# M051B.net
KiCad netlist of a schematic drawn in EAGLE
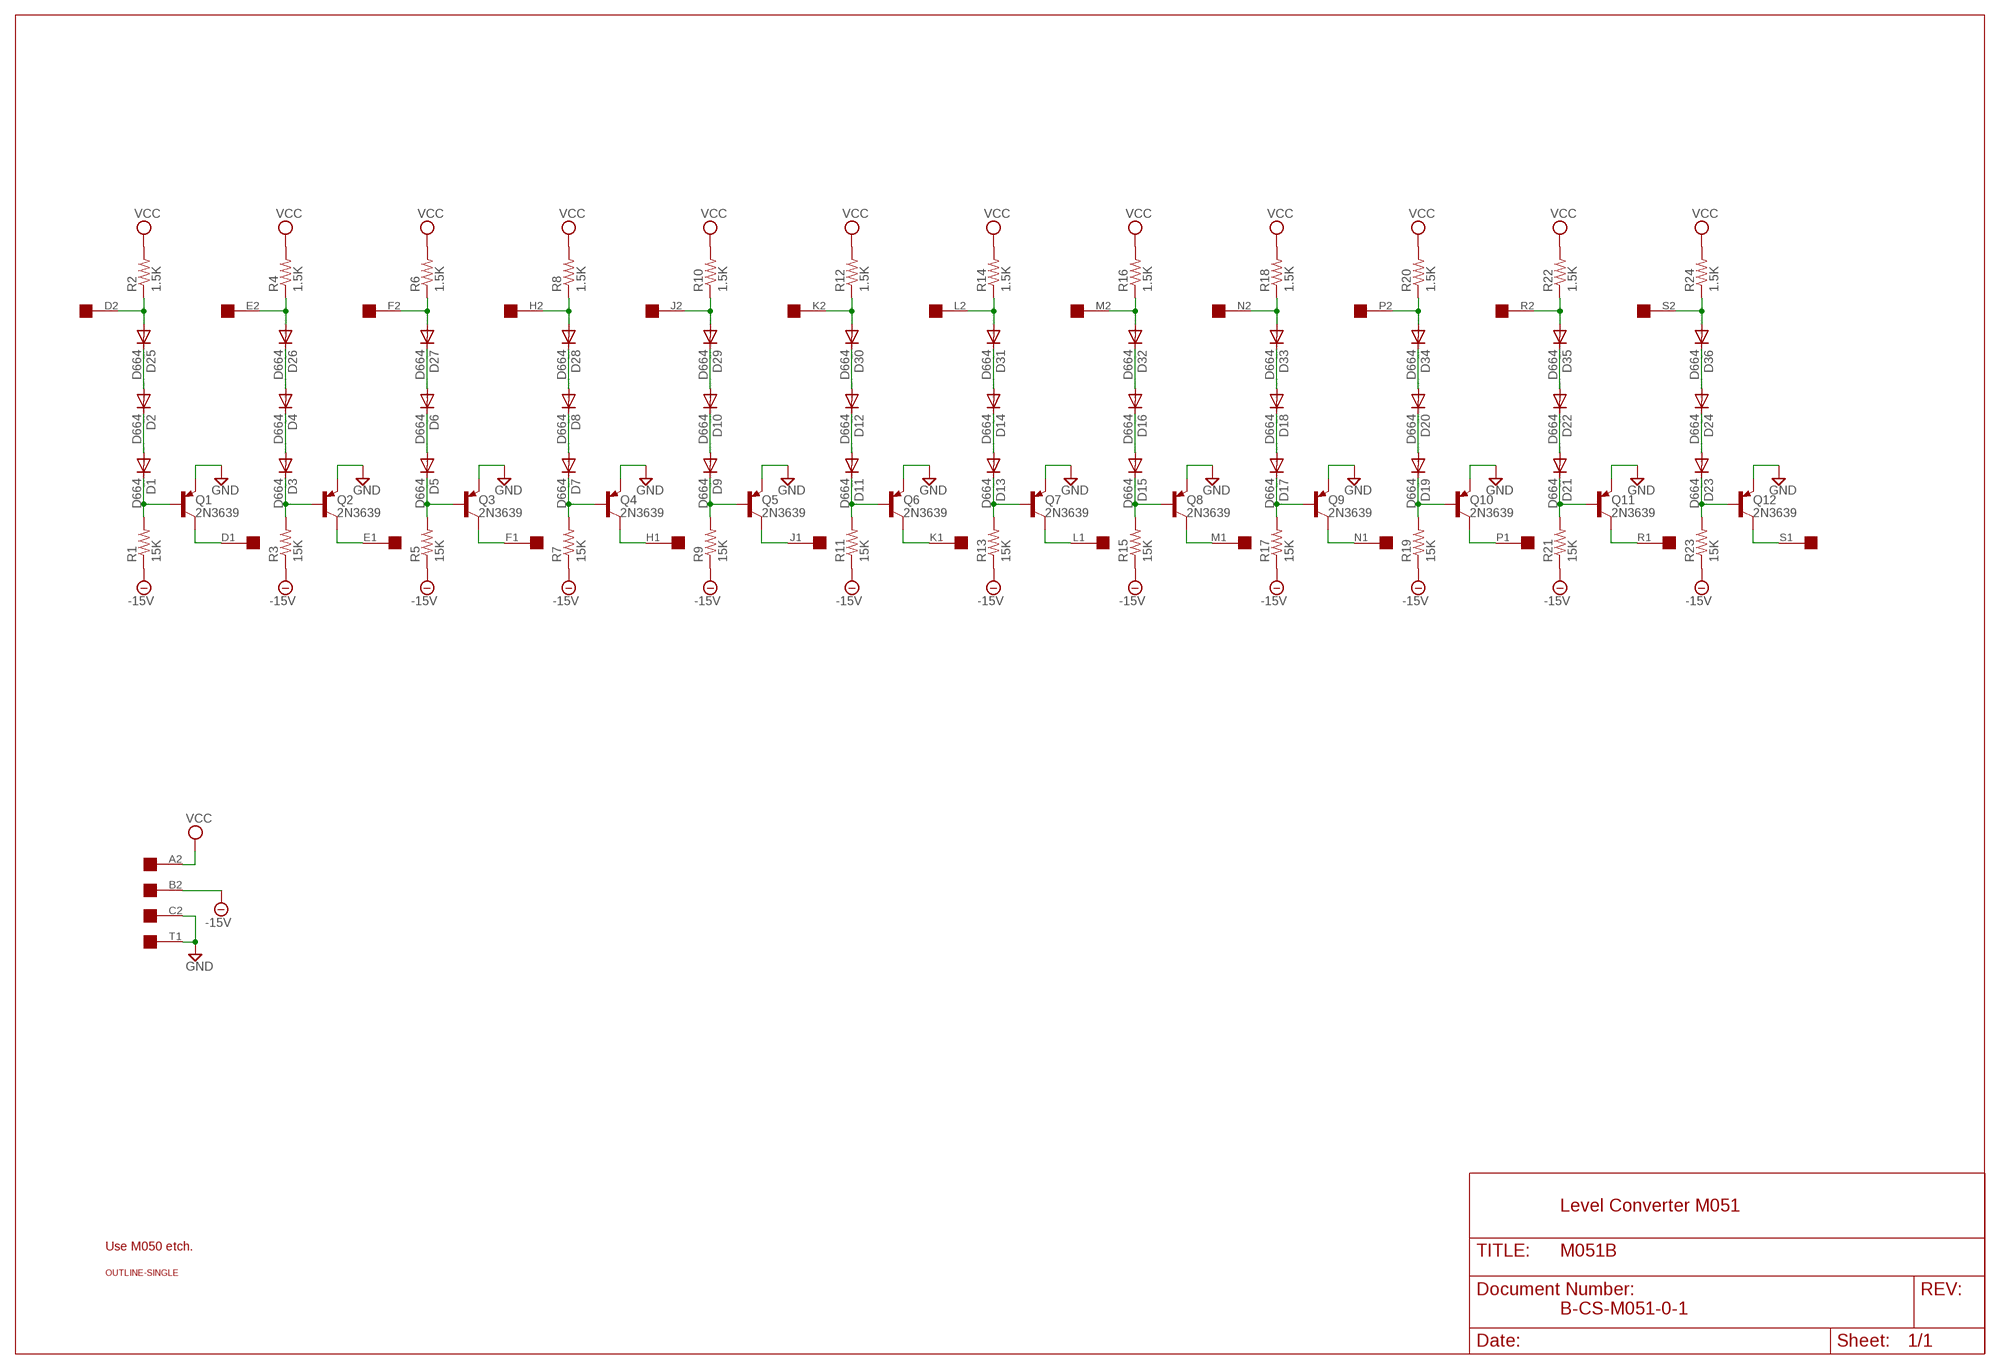
[diagram p0: schematic, sheet 1]

(export (version "E")
  (design (tool "Eeschema 10.0.6"))
  (components
    (comp (ref "D1")
      (value "D664")
      (footprint "eagle-import:DO35-10")
      (libsource (lib "eagle-import") (part "DIODE-DO35-10"))
    )
    (comp (ref "D2")
      (value "D664")
      (footprint "eagle-import:DO35-10")
      (libsource (lib "eagle-import") (part "DIODE-DO35-10"))
    )
    (comp (ref "D3")
      (value "D664")
      (footprint "eagle-import:DO35-10")
      (libsource (lib "eagle-import") (part "DIODE-DO35-10"))
    )
    (comp (ref "D4")
      (value "D664")
      (footprint "eagle-import:DO35-10")
      (libsource (lib "eagle-import") (part "DIODE-DO35-10"))
    )
    (comp (ref "D5")
      (value "D664")
      (footprint "eagle-import:DO35-10")
      (libsource (lib "eagle-import") (part "DIODE-DO35-10"))
    )
    (comp (ref "D6")
      (value "D664")
      (footprint "eagle-import:DO35-10")
      (libsource (lib "eagle-import") (part "DIODE-DO35-10"))
    )
    (comp (ref "D7")
      (value "D664")
      (footprint "eagle-import:DO35-10")
      (libsource (lib "eagle-import") (part "DIODE-DO35-10"))
    )
    (comp (ref "D8")
      (value "D664")
      (footprint "eagle-import:DO35-10")
      (libsource (lib "eagle-import") (part "DIODE-DO35-10"))
    )
    (comp (ref "D9")
      (value "D664")
      (footprint "eagle-import:DO35-10")
      (libsource (lib "eagle-import") (part "DIODE-DO35-10"))
    )
    (comp (ref "D10")
      (value "D664")
      (footprint "eagle-import:DO35-10")
      (libsource (lib "eagle-import") (part "DIODE-DO35-10"))
    )
    (comp (ref "D11")
      (value "D664")
      (footprint "eagle-import:DO35-10")
      (libsource (lib "eagle-import") (part "DIODE-DO35-10"))
    )
    (comp (ref "D12")
      (value "D664")
      (footprint "eagle-import:DO35-10")
      (libsource (lib "eagle-import") (part "DIODE-DO35-10"))
    )
    (comp (ref "D13")
      (value "D664")
      (footprint "eagle-import:DO35-10")
      (libsource (lib "eagle-import") (part "DIODE-DO35-10"))
    )
    (comp (ref "D14")
      (value "D664")
      (footprint "eagle-import:DO35-10")
      (libsource (lib "eagle-import") (part "DIODE-DO35-10"))
    )
    (comp (ref "D15")
      (value "D664")
      (footprint "eagle-import:DO35-10")
      (libsource (lib "eagle-import") (part "DIODE-DO35-10"))
    )
    (comp (ref "D16")
      (value "D664")
      (footprint "eagle-import:DO35-10")
      (libsource (lib "eagle-import") (part "DIODE-DO35-10"))
    )
    (comp (ref "D17")
      (value "D664")
      (footprint "eagle-import:DO35-10")
      (libsource (lib "eagle-import") (part "DIODE-DO35-10"))
    )
    (comp (ref "D18")
      (value "D664")
      (footprint "eagle-import:DO35-10")
      (libsource (lib "eagle-import") (part "DIODE-DO35-10"))
    )
    (comp (ref "D19")
      (value "D664")
      (footprint "eagle-import:DO35-10")
      (libsource (lib "eagle-import") (part "DIODE-DO35-10"))
    )
    (comp (ref "D20")
      (value "D664")
      (footprint "eagle-import:DO35-10")
      (libsource (lib "eagle-import") (part "DIODE-DO35-10"))
    )
    (comp (ref "D21")
      (value "D664")
      (footprint "eagle-import:DO35-10")
      (libsource (lib "eagle-import") (part "DIODE-DO35-10"))
    )
    (comp (ref "D22")
      (value "D664")
      (footprint "eagle-import:DO35-10")
      (libsource (lib "eagle-import") (part "DIODE-DO35-10"))
    )
    (comp (ref "D23")
      (value "D664")
      (footprint "eagle-import:DO35-10")
      (libsource (lib "eagle-import") (part "DIODE-DO35-10"))
    )
    (comp (ref "D24")
      (value "D664")
      (footprint "eagle-import:DO35-10")
      (libsource (lib "eagle-import") (part "DIODE-DO35-10"))
    )
    (comp (ref "D25")
      (value "D664")
      (footprint "eagle-import:DO35-10")
      (libsource (lib "eagle-import") (part "DIODE-DO35-10"))
    )
    (comp (ref "D26")
      (value "D664")
      (footprint "eagle-import:DO35-10")
      (libsource (lib "eagle-import") (part "DIODE-DO35-10"))
    )
    (comp (ref "D27")
      (value "D664")
      (footprint "eagle-import:DO35-10")
      (libsource (lib "eagle-import") (part "DIODE-DO35-10"))
    )
    (comp (ref "D28")
      (value "D664")
      (footprint "eagle-import:DO35-10")
      (libsource (lib "eagle-import") (part "DIODE-DO35-10"))
    )
    (comp (ref "D29")
      (value "D664")
      (footprint "eagle-import:DO35-10")
      (libsource (lib "eagle-import") (part "DIODE-DO35-10"))
    )
    (comp (ref "D30")
      (value "D664")
      (footprint "eagle-import:DO35-10")
      (libsource (lib "eagle-import") (part "DIODE-DO35-10"))
    )
    (comp (ref "D31")
      (value "D664")
      (footprint "eagle-import:DO35-10")
      (libsource (lib "eagle-import") (part "DIODE-DO35-10"))
    )
    (comp (ref "D32")
      (value "D664")
      (footprint "eagle-import:DO35-10")
      (libsource (lib "eagle-import") (part "DIODE-DO35-10"))
    )
    (comp (ref "D33")
      (value "D664")
      (footprint "eagle-import:DO35-10")
      (libsource (lib "eagle-import") (part "DIODE-DO35-10"))
    )
    (comp (ref "D34")
      (value "D664")
      (footprint "eagle-import:DO35-10")
      (libsource (lib "eagle-import") (part "DIODE-DO35-10"))
    )
    (comp (ref "D35")
      (value "D664")
      (footprint "eagle-import:DO35-10")
      (libsource (lib "eagle-import") (part "DIODE-DO35-10"))
    )
    (comp (ref "D36")
      (value "D664")
      (footprint "eagle-import:DO35-10")
      (libsource (lib "eagle-import") (part "DIODE-DO35-10"))
    )
    (comp (ref "Q1")
      (value "2N3639")
      (footprint "eagle-import:TO5")
      (libsource (lib "eagle-import") (part "-PNP-TO5"))
    )
    (comp (ref "Q2")
      (value "2N3639")
      (footprint "eagle-import:TO5")
      (libsource (lib "eagle-import") (part "-PNP-TO5"))
    )
    (comp (ref "Q3")
      (value "2N3639")
      (footprint "eagle-import:TO5")
      (libsource (lib "eagle-import") (part "-PNP-TO5"))
    )
    (comp (ref "Q4")
      (value "2N3639")
      (footprint "eagle-import:TO5")
      (libsource (lib "eagle-import") (part "-PNP-TO5"))
    )
    (comp (ref "Q5")
      (value "2N3639")
      (footprint "eagle-import:TO5")
      (libsource (lib "eagle-import") (part "-PNP-TO5"))
    )
    (comp (ref "Q6")
      (value "2N3639")
      (footprint "eagle-import:TO5")
      (libsource (lib "eagle-import") (part "-PNP-TO5"))
    )
    (comp (ref "Q7")
      (value "2N3639")
      (footprint "eagle-import:TO5")
      (libsource (lib "eagle-import") (part "-PNP-TO5"))
    )
    (comp (ref "Q8")
      (value "2N3639")
      (footprint "eagle-import:TO5")
      (libsource (lib "eagle-import") (part "-PNP-TO5"))
    )
    (comp (ref "Q9")
      (value "2N3639")
      (footprint "eagle-import:TO5")
      (libsource (lib "eagle-import") (part "-PNP-TO5"))
    )
    (comp (ref "Q10")
      (value "2N3639")
      (footprint "eagle-import:TO5")
      (libsource (lib "eagle-import") (part "-PNP-TO5"))
    )
    (comp (ref "Q11")
      (value "2N3639")
      (footprint "eagle-import:TO5")
      (libsource (lib "eagle-import") (part "-PNP-TO5"))
    )
    (comp (ref "Q12")
      (value "2N3639")
      (footprint "eagle-import:TO5")
      (libsource (lib "eagle-import") (part "-PNP-TO5"))
    )
    (comp (ref "R1")
      (value "15K")
      (footprint "eagle-import:0207_10")
      (libsource (lib "eagle-import") (part "R-US_0207/10"))
    )
    (comp (ref "R2")
      (value "1.5K")
      (footprint "eagle-import:0207_10")
      (libsource (lib "eagle-import") (part "R-US_0207/10"))
    )
    (comp (ref "R3")
      (value "15K")
      (footprint "eagle-import:0207_10")
      (libsource (lib "eagle-import") (part "R-US_0207/10"))
    )
    (comp (ref "R4")
      (value "1.5K")
      (footprint "eagle-import:0207_10")
      (libsource (lib "eagle-import") (part "R-US_0207/10"))
    )
    (comp (ref "R5")
      (value "15K")
      (footprint "eagle-import:0207_10")
      (libsource (lib "eagle-import") (part "R-US_0207/10"))
    )
    (comp (ref "R6")
      (value "1.5K")
      (footprint "eagle-import:0207_10")
      (libsource (lib "eagle-import") (part "R-US_0207/10"))
    )
    (comp (ref "R7")
      (value "15K")
      (footprint "eagle-import:0207_10")
      (libsource (lib "eagle-import") (part "R-US_0207/10"))
    )
    (comp (ref "R8")
      (value "1.5K")
      (footprint "eagle-import:0207_10")
      (libsource (lib "eagle-import") (part "R-US_0207/10"))
    )
    (comp (ref "R9")
      (value "15K")
      (footprint "eagle-import:0207_10")
      (libsource (lib "eagle-import") (part "R-US_0207/10"))
    )
    (comp (ref "R10")
      (value "1.5K")
      (footprint "eagle-import:0207_10")
      (libsource (lib "eagle-import") (part "R-US_0207/10"))
    )
    (comp (ref "R11")
      (value "15K")
      (footprint "eagle-import:0207_10")
      (libsource (lib "eagle-import") (part "R-US_0207/10"))
    )
    (comp (ref "R12")
      (value "1.5K")
      (footprint "eagle-import:0207_10")
      (libsource (lib "eagle-import") (part "R-US_0207/10"))
    )
    (comp (ref "R13")
      (value "15K")
      (footprint "eagle-import:0207_10")
      (libsource (lib "eagle-import") (part "R-US_0207/10"))
    )
    (comp (ref "R14")
      (value "1.5K")
      (footprint "eagle-import:0207_10")
      (libsource (lib "eagle-import") (part "R-US_0207/10"))
    )
    (comp (ref "R15")
      (value "15K")
      (footprint "eagle-import:0207_10")
      (libsource (lib "eagle-import") (part "R-US_0207/10"))
    )
    (comp (ref "R16")
      (value "1.5K")
      (footprint "eagle-import:0207_10")
      (libsource (lib "eagle-import") (part "R-US_0207/10"))
    )
    (comp (ref "R17")
      (value "15K")
      (footprint "eagle-import:0207_10")
      (libsource (lib "eagle-import") (part "R-US_0207/10"))
    )
    (comp (ref "R18")
      (value "1.5K")
      (footprint "eagle-import:0207_10")
      (libsource (lib "eagle-import") (part "R-US_0207/10"))
    )
    (comp (ref "R19")
      (value "15K")
      (footprint "eagle-import:0207_10")
      (libsource (lib "eagle-import") (part "R-US_0207/10"))
    )
    (comp (ref "R20")
      (value "1.5K")
      (footprint "eagle-import:0207_10")
      (libsource (lib "eagle-import") (part "R-US_0207/10"))
    )
    (comp (ref "R21")
      (value "15K")
      (footprint "eagle-import:0207_10")
      (libsource (lib "eagle-import") (part "R-US_0207/10"))
    )
    (comp (ref "R22")
      (value "1.5K")
      (footprint "eagle-import:0207_10")
      (libsource (lib "eagle-import") (part "R-US_0207/10"))
    )
    (comp (ref "R23")
      (value "15K")
      (footprint "eagle-import:0207_10")
      (libsource (lib "eagle-import") (part "R-US_0207/10"))
    )
    (comp (ref "R24")
      (value "1.5K")
      (footprint "eagle-import:0207_10")
      (libsource (lib "eagle-import") (part "R-US_0207/10"))
    )
    (comp (ref "U$1")
      (value "OUTLINE-SINGLE")
      (footprint "eagle-import:SINGLE")
      (libsource (lib "eagle-import") (part "OUTLINE-SINGLE"))
    )
    (comp (ref "U$2")
      (value "SINGLE")
      (footprint "eagle-import:EDGE-CON2")
      (libsource (lib "eagle-import") (part "SINGLE"))
    )
  )
  (nets
    (net (code "1") (name "-15V") (class "Default")
      (node (ref "R1") (pin "1") (pinfunction "1_1") (pintype "passive"))
      (node (ref "R11") (pin "1") (pinfunction "1_1") (pintype "passive"))
      (node (ref "R13") (pin "1") (pinfunction "1_1") (pintype "passive"))
      (node (ref "R15") (pin "1") (pinfunction "1_1") (pintype "passive"))
      (node (ref "R17") (pin "1") (pinfunction "1_1") (pintype "passive"))
      (node (ref "R19") (pin "1") (pinfunction "1_1") (pintype "passive"))
      (node (ref "R21") (pin "1") (pinfunction "1_1") (pintype "passive"))
      (node (ref "R23") (pin "1") (pinfunction "1_1") (pintype "passive"))
      (node (ref "R3") (pin "1") (pinfunction "1_1") (pintype "passive"))
      (node (ref "R5") (pin "1") (pinfunction "1_1") (pintype "passive"))
      (node (ref "R7") (pin "1") (pinfunction "1_1") (pintype "passive"))
      (node (ref "R9") (pin "1") (pinfunction "1_1") (pintype "passive"))
      (node (ref "U$2") (pin "B2") (pinfunction "1_B2") (pintype "bidirectional"))
    )
    (net (code "2") (name "GND") (class "Default")
      (node (ref "Q1") (pin "1") (pinfunction "E_1") (pintype "passive"))
      (node (ref "Q10") (pin "1") (pinfunction "E_1") (pintype "passive"))
      (node (ref "Q11") (pin "1") (pinfunction "E_1") (pintype "passive"))
      (node (ref "Q12") (pin "1") (pinfunction "E_1") (pintype "passive"))
      (node (ref "Q2") (pin "1") (pinfunction "E_1") (pintype "passive"))
      (node (ref "Q3") (pin "1") (pinfunction "E_1") (pintype "passive"))
      (node (ref "Q4") (pin "1") (pinfunction "E_1") (pintype "passive"))
      (node (ref "Q5") (pin "1") (pinfunction "E_1") (pintype "passive"))
      (node (ref "Q6") (pin "1") (pinfunction "E_1") (pintype "passive"))
      (node (ref "Q7") (pin "1") (pinfunction "E_1") (pintype "passive"))
      (node (ref "Q8") (pin "1") (pinfunction "E_1") (pintype "passive"))
      (node (ref "Q9") (pin "1") (pinfunction "E_1") (pintype "passive"))
      (node (ref "U$2") (pin "C2") (pinfunction "1_C2") (pintype "bidirectional"))
      (node (ref "U$2") (pin "T1") (pinfunction "1_T1") (pintype "bidirectional"))
    )
    (net (code "3") (name "Net-(D1-PadA)") (class "Default")
      (node (ref "D1") (pin "A") (pinfunction "A_A") (pintype "passive"))
      (node (ref "D2") (pin "C") (pinfunction "C_C") (pintype "passive"))
    )
    (net (code "4") (name "Net-(D2-PadA)") (class "Default")
      (node (ref "D2") (pin "A") (pinfunction "A_A") (pintype "passive"))
      (node (ref "D25") (pin "C") (pinfunction "C_C") (pintype "passive"))
    )
    (net (code "5") (name "Net-(D3-PadA)") (class "Default")
      (node (ref "D3") (pin "A") (pinfunction "A_A") (pintype "passive"))
      (node (ref "D4") (pin "C") (pinfunction "C_C") (pintype "passive"))
    )
    (net (code "6") (name "Net-(D5-PadA)") (class "Default")
      (node (ref "D5") (pin "A") (pinfunction "A_A") (pintype "passive"))
      (node (ref "D6") (pin "C") (pinfunction "C_C") (pintype "passive"))
    )
    (net (code "7") (name "Net-(D7-PadA)") (class "Default")
      (node (ref "D7") (pin "A") (pinfunction "A_A") (pintype "passive"))
      (node (ref "D8") (pin "C") (pinfunction "C_C") (pintype "passive"))
    )
    (net (code "8") (name "Net-(D10-PadA)") (class "Default")
      (node (ref "D10") (pin "A") (pinfunction "A_A") (pintype "passive"))
      (node (ref "D29") (pin "C") (pinfunction "C_C") (pintype "passive"))
    )
    (net (code "9") (name "Net-(D10-PadC)") (class "Default")
      (node (ref "D10") (pin "C") (pinfunction "C_C") (pintype "passive"))
      (node (ref "D9") (pin "A") (pinfunction "A_A") (pintype "passive"))
    )
    (net (code "10") (name "Net-(D11-PadA)") (class "Default")
      (node (ref "D11") (pin "A") (pinfunction "A_A") (pintype "passive"))
      (node (ref "D12") (pin "C") (pinfunction "C_C") (pintype "passive"))
    )
    (net (code "11") (name "Net-(D12-PadA)") (class "Default")
      (node (ref "D12") (pin "A") (pinfunction "A_A") (pintype "passive"))
      (node (ref "D30") (pin "C") (pinfunction "C_C") (pintype "passive"))
    )
    (net (code "12") (name "Net-(D13-PadA)") (class "Default")
      (node (ref "D13") (pin "A") (pinfunction "A_A") (pintype "passive"))
      (node (ref "D14") (pin "C") (pinfunction "C_C") (pintype "passive"))
    )
    (net (code "13") (name "Net-(D14-PadA)") (class "Default")
      (node (ref "D14") (pin "A") (pinfunction "A_A") (pintype "passive"))
      (node (ref "D31") (pin "C") (pinfunction "C_C") (pintype "passive"))
    )
    (net (code "14") (name "Net-(D15-PadA)") (class "Default")
      (node (ref "D15") (pin "A") (pinfunction "A_A") (pintype "passive"))
      (node (ref "D16") (pin "C") (pinfunction "C_C") (pintype "passive"))
    )
    (net (code "15") (name "Net-(D16-PadA)") (class "Default")
      (node (ref "D16") (pin "A") (pinfunction "A_A") (pintype "passive"))
      (node (ref "D32") (pin "C") (pinfunction "C_C") (pintype "passive"))
    )
    (net (code "16") (name "Net-(D17-PadA)") (class "Default")
      (node (ref "D17") (pin "A") (pinfunction "A_A") (pintype "passive"))
      (node (ref "D18") (pin "C") (pinfunction "C_C") (pintype "passive"))
    )
    (net (code "17") (name "Net-(D18-PadA)") (class "Default")
      (node (ref "D18") (pin "A") (pinfunction "A_A") (pintype "passive"))
      (node (ref "D33") (pin "C") (pinfunction "C_C") (pintype "passive"))
    )
    (net (code "18") (name "Net-(D19-PadA)") (class "Default")
      (node (ref "D19") (pin "A") (pinfunction "A_A") (pintype "passive"))
      (node (ref "D20") (pin "C") (pinfunction "C_C") (pintype "passive"))
    )
    (net (code "19") (name "Net-(D20-PadA)") (class "Default")
      (node (ref "D20") (pin "A") (pinfunction "A_A") (pintype "passive"))
      (node (ref "D34") (pin "C") (pinfunction "C_C") (pintype "passive"))
    )
    (net (code "20") (name "Net-(D21-PadA)") (class "Default")
      (node (ref "D21") (pin "A") (pinfunction "A_A") (pintype "passive"))
      (node (ref "D22") (pin "C") (pinfunction "C_C") (pintype "passive"))
    )
    (net (code "21") (name "Net-(D22-PadA)") (class "Default")
      (node (ref "D22") (pin "A") (pinfunction "A_A") (pintype "passive"))
      (node (ref "D35") (pin "C") (pinfunction "C_C") (pintype "passive"))
    )
    (net (code "22") (name "Net-(D23-PadA)") (class "Default")
      (node (ref "D23") (pin "A") (pinfunction "A_A") (pintype "passive"))
      (node (ref "D24") (pin "C") (pinfunction "C_C") (pintype "passive"))
    )
    (net (code "23") (name "Net-(D24-PadA)") (class "Default")
      (node (ref "D24") (pin "A") (pinfunction "A_A") (pintype "passive"))
      (node (ref "D36") (pin "C") (pinfunction "C_C") (pintype "passive"))
    )
    (net (code "24") (name "Net-(D26-PadC)") (class "Default")
      (node (ref "D26") (pin "C") (pinfunction "C_C") (pintype "passive"))
      (node (ref "D4") (pin "A") (pinfunction "A_A") (pintype "passive"))
    )
    (net (code "25") (name "Net-(D27-PadC)") (class "Default")
      (node (ref "D27") (pin "C") (pinfunction "C_C") (pintype "passive"))
      (node (ref "D6") (pin "A") (pinfunction "A_A") (pintype "passive"))
    )
    (net (code "26") (name "Net-(D28-PadC)") (class "Default")
      (node (ref "D28") (pin "C") (pinfunction "C_C") (pintype "passive"))
      (node (ref "D8") (pin "A") (pinfunction "A_A") (pintype "passive"))
    )
    (net (code "27") (name "Net-(Q1-B)") (class "Default")
      (node (ref "D1") (pin "C") (pinfunction "C_C") (pintype "passive"))
      (node (ref "Q1") (pin "2") (pinfunction "B_2") (pintype "passive"))
      (node (ref "R1") (pin "2") (pinfunction "2_2") (pintype "passive"))
    )
    (net (code "28") (name "Net-(Q1-C)") (class "Default")
      (node (ref "Q1") (pin "3") (pinfunction "C_3") (pintype "passive"))
      (node (ref "U$2") (pin "D1") (pinfunction "1_D1") (pintype "bidirectional"))
    )
    (net (code "29") (name "Net-(Q2-B)") (class "Default")
      (node (ref "D3") (pin "C") (pinfunction "C_C") (pintype "passive"))
      (node (ref "Q2") (pin "2") (pinfunction "B_2") (pintype "passive"))
      (node (ref "R3") (pin "2") (pinfunction "2_2") (pintype "passive"))
    )
    (net (code "30") (name "Net-(Q2-C)") (class "Default")
      (node (ref "Q2") (pin "3") (pinfunction "C_3") (pintype "passive"))
      (node (ref "U$2") (pin "E1") (pinfunction "1_E1") (pintype "bidirectional"))
    )
    (net (code "31") (name "Net-(Q3-B)") (class "Default")
      (node (ref "D5") (pin "C") (pinfunction "C_C") (pintype "passive"))
      (node (ref "Q3") (pin "2") (pinfunction "B_2") (pintype "passive"))
      (node (ref "R5") (pin "2") (pinfunction "2_2") (pintype "passive"))
    )
    (net (code "32") (name "Net-(Q3-C)") (class "Default")
      (node (ref "Q3") (pin "3") (pinfunction "C_3") (pintype "passive"))
      (node (ref "U$2") (pin "F1") (pinfunction "1_F1") (pintype "bidirectional"))
    )
    (net (code "33") (name "Net-(Q4-B)") (class "Default")
      (node (ref "D7") (pin "C") (pinfunction "C_C") (pintype "passive"))
      (node (ref "Q4") (pin "2") (pinfunction "B_2") (pintype "passive"))
      (node (ref "R7") (pin "2") (pinfunction "2_2") (pintype "passive"))
    )
    (net (code "34") (name "Net-(Q4-C)") (class "Default")
      (node (ref "Q4") (pin "3") (pinfunction "C_3") (pintype "passive"))
      (node (ref "U$2") (pin "H1") (pinfunction "1_H1") (pintype "bidirectional"))
    )
    (net (code "35") (name "Net-(Q5-B)") (class "Default")
      (node (ref "D9") (pin "C") (pinfunction "C_C") (pintype "passive"))
      (node (ref "Q5") (pin "2") (pinfunction "B_2") (pintype "passive"))
      (node (ref "R9") (pin "2") (pinfunction "2_2") (pintype "passive"))
    )
    (net (code "36") (name "Net-(Q5-C)") (class "Default")
      (node (ref "Q5") (pin "3") (pinfunction "C_3") (pintype "passive"))
      (node (ref "U$2") (pin "J1") (pinfunction "1_J1") (pintype "bidirectional"))
    )
    (net (code "37") (name "Net-(Q6-B)") (class "Default")
      (node (ref "D11") (pin "C") (pinfunction "C_C") (pintype "passive"))
      (node (ref "Q6") (pin "2") (pinfunction "B_2") (pintype "passive"))
      (node (ref "R11") (pin "2") (pinfunction "2_2") (pintype "passive"))
    )
    (net (code "38") (name "Net-(Q6-C)") (class "Default")
      (node (ref "Q6") (pin "3") (pinfunction "C_3") (pintype "passive"))
      (node (ref "U$2") (pin "K1") (pinfunction "1_K1") (pintype "bidirectional"))
    )
    (net (code "39") (name "Net-(Q7-B)") (class "Default")
      (node (ref "D13") (pin "C") (pinfunction "C_C") (pintype "passive"))
      (node (ref "Q7") (pin "2") (pinfunction "B_2") (pintype "passive"))
      (node (ref "R13") (pin "2") (pinfunction "2_2") (pintype "passive"))
    )
    (net (code "40") (name "Net-(Q7-C)") (class "Default")
      (node (ref "Q7") (pin "3") (pinfunction "C_3") (pintype "passive"))
      (node (ref "U$2") (pin "L1") (pinfunction "1_L1") (pintype "bidirectional"))
    )
    (net (code "41") (name "Net-(Q8-B)") (class "Default")
      (node (ref "D15") (pin "C") (pinfunction "C_C") (pintype "passive"))
      (node (ref "Q8") (pin "2") (pinfunction "B_2") (pintype "passive"))
      (node (ref "R15") (pin "2") (pinfunction "2_2") (pintype "passive"))
    )
    (net (code "42") (name "Net-(Q8-C)") (class "Default")
      (node (ref "Q8") (pin "3") (pinfunction "C_3") (pintype "passive"))
      (node (ref "U$2") (pin "M1") (pinfunction "1_M1") (pintype "bidirectional"))
    )
    (net (code "43") (name "Net-(Q9-B)") (class "Default")
      (node (ref "D17") (pin "C") (pinfunction "C_C") (pintype "passive"))
      (node (ref "Q9") (pin "2") (pinfunction "B_2") (pintype "passive"))
      (node (ref "R17") (pin "2") (pinfunction "2_2") (pintype "passive"))
    )
    (net (code "44") (name "Net-(Q9-C)") (class "Default")
      (node (ref "Q9") (pin "3") (pinfunction "C_3") (pintype "passive"))
      (node (ref "U$2") (pin "N1") (pinfunction "1_N1") (pintype "bidirectional"))
    )
    (net (code "45") (name "Net-(Q10-B)") (class "Default")
      (node (ref "D19") (pin "C") (pinfunction "C_C") (pintype "passive"))
      (node (ref "Q10") (pin "2") (pinfunction "B_2") (pintype "passive"))
      (node (ref "R19") (pin "2") (pinfunction "2_2") (pintype "passive"))
    )
    (net (code "46") (name "Net-(Q10-C)") (class "Default")
      (node (ref "Q10") (pin "3") (pinfunction "C_3") (pintype "passive"))
      (node (ref "U$2") (pin "P1") (pinfunction "1_P1") (pintype "bidirectional"))
    )
    (net (code "47") (name "Net-(Q11-B)") (class "Default")
      (node (ref "D21") (pin "C") (pinfunction "C_C") (pintype "passive"))
      (node (ref "Q11") (pin "2") (pinfunction "B_2") (pintype "passive"))
      (node (ref "R21") (pin "2") (pinfunction "2_2") (pintype "passive"))
    )
    (net (code "48") (name "Net-(Q11-C)") (class "Default")
      (node (ref "Q11") (pin "3") (pinfunction "C_3") (pintype "passive"))
      (node (ref "U$2") (pin "R1") (pinfunction "1_R1") (pintype "bidirectional"))
    )
    (net (code "49") (name "Net-(Q12-B)") (class "Default")
      (node (ref "D23") (pin "C") (pinfunction "C_C") (pintype "passive"))
      (node (ref "Q12") (pin "2") (pinfunction "B_2") (pintype "passive"))
      (node (ref "R23") (pin "2") (pinfunction "2_2") (pintype "passive"))
    )
    (net (code "50") (name "Net-(Q12-C)") (class "Default")
      (node (ref "Q12") (pin "3") (pinfunction "C_3") (pintype "passive"))
      (node (ref "U$2") (pin "S1") (pinfunction "1_S1") (pintype "bidirectional"))
    )
    (net (code "51") (name "Net-(U$2AB-1)") (class "Default")
      (node (ref "D35") (pin "A") (pinfunction "A_A") (pintype "passive"))
      (node (ref "R22") (pin "1") (pinfunction "1_1") (pintype "passive"))
      (node (ref "U$2") (pin "R2") (pinfunction "1_R2") (pintype "bidirectional"))
    )
    (net (code "52") (name "Net-(U$2AD-1)") (class "Default")
      (node (ref "D36") (pin "A") (pinfunction "A_A") (pintype "passive"))
      (node (ref "R24") (pin "1") (pinfunction "1_1") (pintype "passive"))
      (node (ref "U$2") (pin "S2") (pinfunction "1_S2") (pintype "bidirectional"))
    )
    (net (code "53") (name "Net-(U$2H-1)") (class "Default")
      (node (ref "D25") (pin "A") (pinfunction "A_A") (pintype "passive"))
      (node (ref "R2") (pin "1") (pinfunction "1_1") (pintype "passive"))
      (node (ref "U$2") (pin "D2") (pinfunction "1_D2") (pintype "bidirectional"))
    )
    (net (code "54") (name "Net-(U$2J-1)") (class "Default")
      (node (ref "D26") (pin "A") (pinfunction "A_A") (pintype "passive"))
      (node (ref "R4") (pin "1") (pinfunction "1_1") (pintype "passive"))
      (node (ref "U$2") (pin "E2") (pinfunction "1_E2") (pintype "bidirectional"))
    )
    (net (code "55") (name "Net-(U$2L-1)") (class "Default")
      (node (ref "D27") (pin "A") (pinfunction "A_A") (pintype "passive"))
      (node (ref "R6") (pin "1") (pinfunction "1_1") (pintype "passive"))
      (node (ref "U$2") (pin "F2") (pinfunction "1_F2") (pintype "bidirectional"))
    )
    (net (code "56") (name "Net-(U$2N-1)") (class "Default")
      (node (ref "D28") (pin "A") (pinfunction "A_A") (pintype "passive"))
      (node (ref "R8") (pin "1") (pinfunction "1_1") (pintype "passive"))
      (node (ref "U$2") (pin "H2") (pinfunction "1_H2") (pintype "bidirectional"))
    )
    (net (code "57") (name "Net-(U$2P-1)") (class "Default")
      (node (ref "D29") (pin "A") (pinfunction "A_A") (pintype "passive"))
      (node (ref "R10") (pin "1") (pinfunction "1_1") (pintype "passive"))
      (node (ref "U$2") (pin "J2") (pinfunction "1_J2") (pintype "bidirectional"))
    )
    (net (code "58") (name "Net-(U$2R-1)") (class "Default")
      (node (ref "D30") (pin "A") (pinfunction "A_A") (pintype "passive"))
      (node (ref "R12") (pin "1") (pinfunction "1_1") (pintype "passive"))
      (node (ref "U$2") (pin "K2") (pinfunction "1_K2") (pintype "bidirectional"))
    )
    (net (code "59") (name "Net-(U$2T-1)") (class "Default")
      (node (ref "D31") (pin "A") (pinfunction "A_A") (pintype "passive"))
      (node (ref "R14") (pin "1") (pinfunction "1_1") (pintype "passive"))
      (node (ref "U$2") (pin "L2") (pinfunction "1_L2") (pintype "bidirectional"))
    )
    (net (code "60") (name "Net-(U$2V-1)") (class "Default")
      (node (ref "D32") (pin "A") (pinfunction "A_A") (pintype "passive"))
      (node (ref "R16") (pin "1") (pinfunction "1_1") (pintype "passive"))
      (node (ref "U$2") (pin "M2") (pinfunction "1_M2") (pintype "bidirectional"))
    )
    (net (code "61") (name "Net-(U$2X-1)") (class "Default")
      (node (ref "D33") (pin "A") (pinfunction "A_A") (pintype "passive"))
      (node (ref "R18") (pin "1") (pinfunction "1_1") (pintype "passive"))
      (node (ref "U$2") (pin "N2") (pinfunction "1_N2") (pintype "bidirectional"))
    )
    (net (code "62") (name "Net-(U$2Z-1)") (class "Default")
      (node (ref "D34") (pin "A") (pinfunction "A_A") (pintype "passive"))
      (node (ref "R20") (pin "1") (pinfunction "1_1") (pintype "passive"))
      (node (ref "U$2") (pin "P2") (pinfunction "1_P2") (pintype "bidirectional"))
    )
    (net (code "63") (name "VCC") (class "Default")
      (node (ref "R10") (pin "2") (pinfunction "2_2") (pintype "passive"))
      (node (ref "R12") (pin "2") (pinfunction "2_2") (pintype "passive"))
      (node (ref "R14") (pin "2") (pinfunction "2_2") (pintype "passive"))
      (node (ref "R16") (pin "2") (pinfunction "2_2") (pintype "passive"))
      (node (ref "R18") (pin "2") (pinfunction "2_2") (pintype "passive"))
      (node (ref "R2") (pin "2") (pinfunction "2_2") (pintype "passive"))
      (node (ref "R20") (pin "2") (pinfunction "2_2") (pintype "passive"))
      (node (ref "R22") (pin "2") (pinfunction "2_2") (pintype "passive"))
      (node (ref "R24") (pin "2") (pinfunction "2_2") (pintype "passive"))
      (node (ref "R4") (pin "2") (pinfunction "2_2") (pintype "passive"))
      (node (ref "R6") (pin "2") (pinfunction "2_2") (pintype "passive"))
      (node (ref "R8") (pin "2") (pinfunction "2_2") (pintype "passive"))
      (node (ref "U$2") (pin "A2") (pinfunction "1_A2") (pintype "bidirectional"))
    )
  )
)
